# tripwire-alarm.net
KiCad netlist of a schematic drawn in EasyEDA
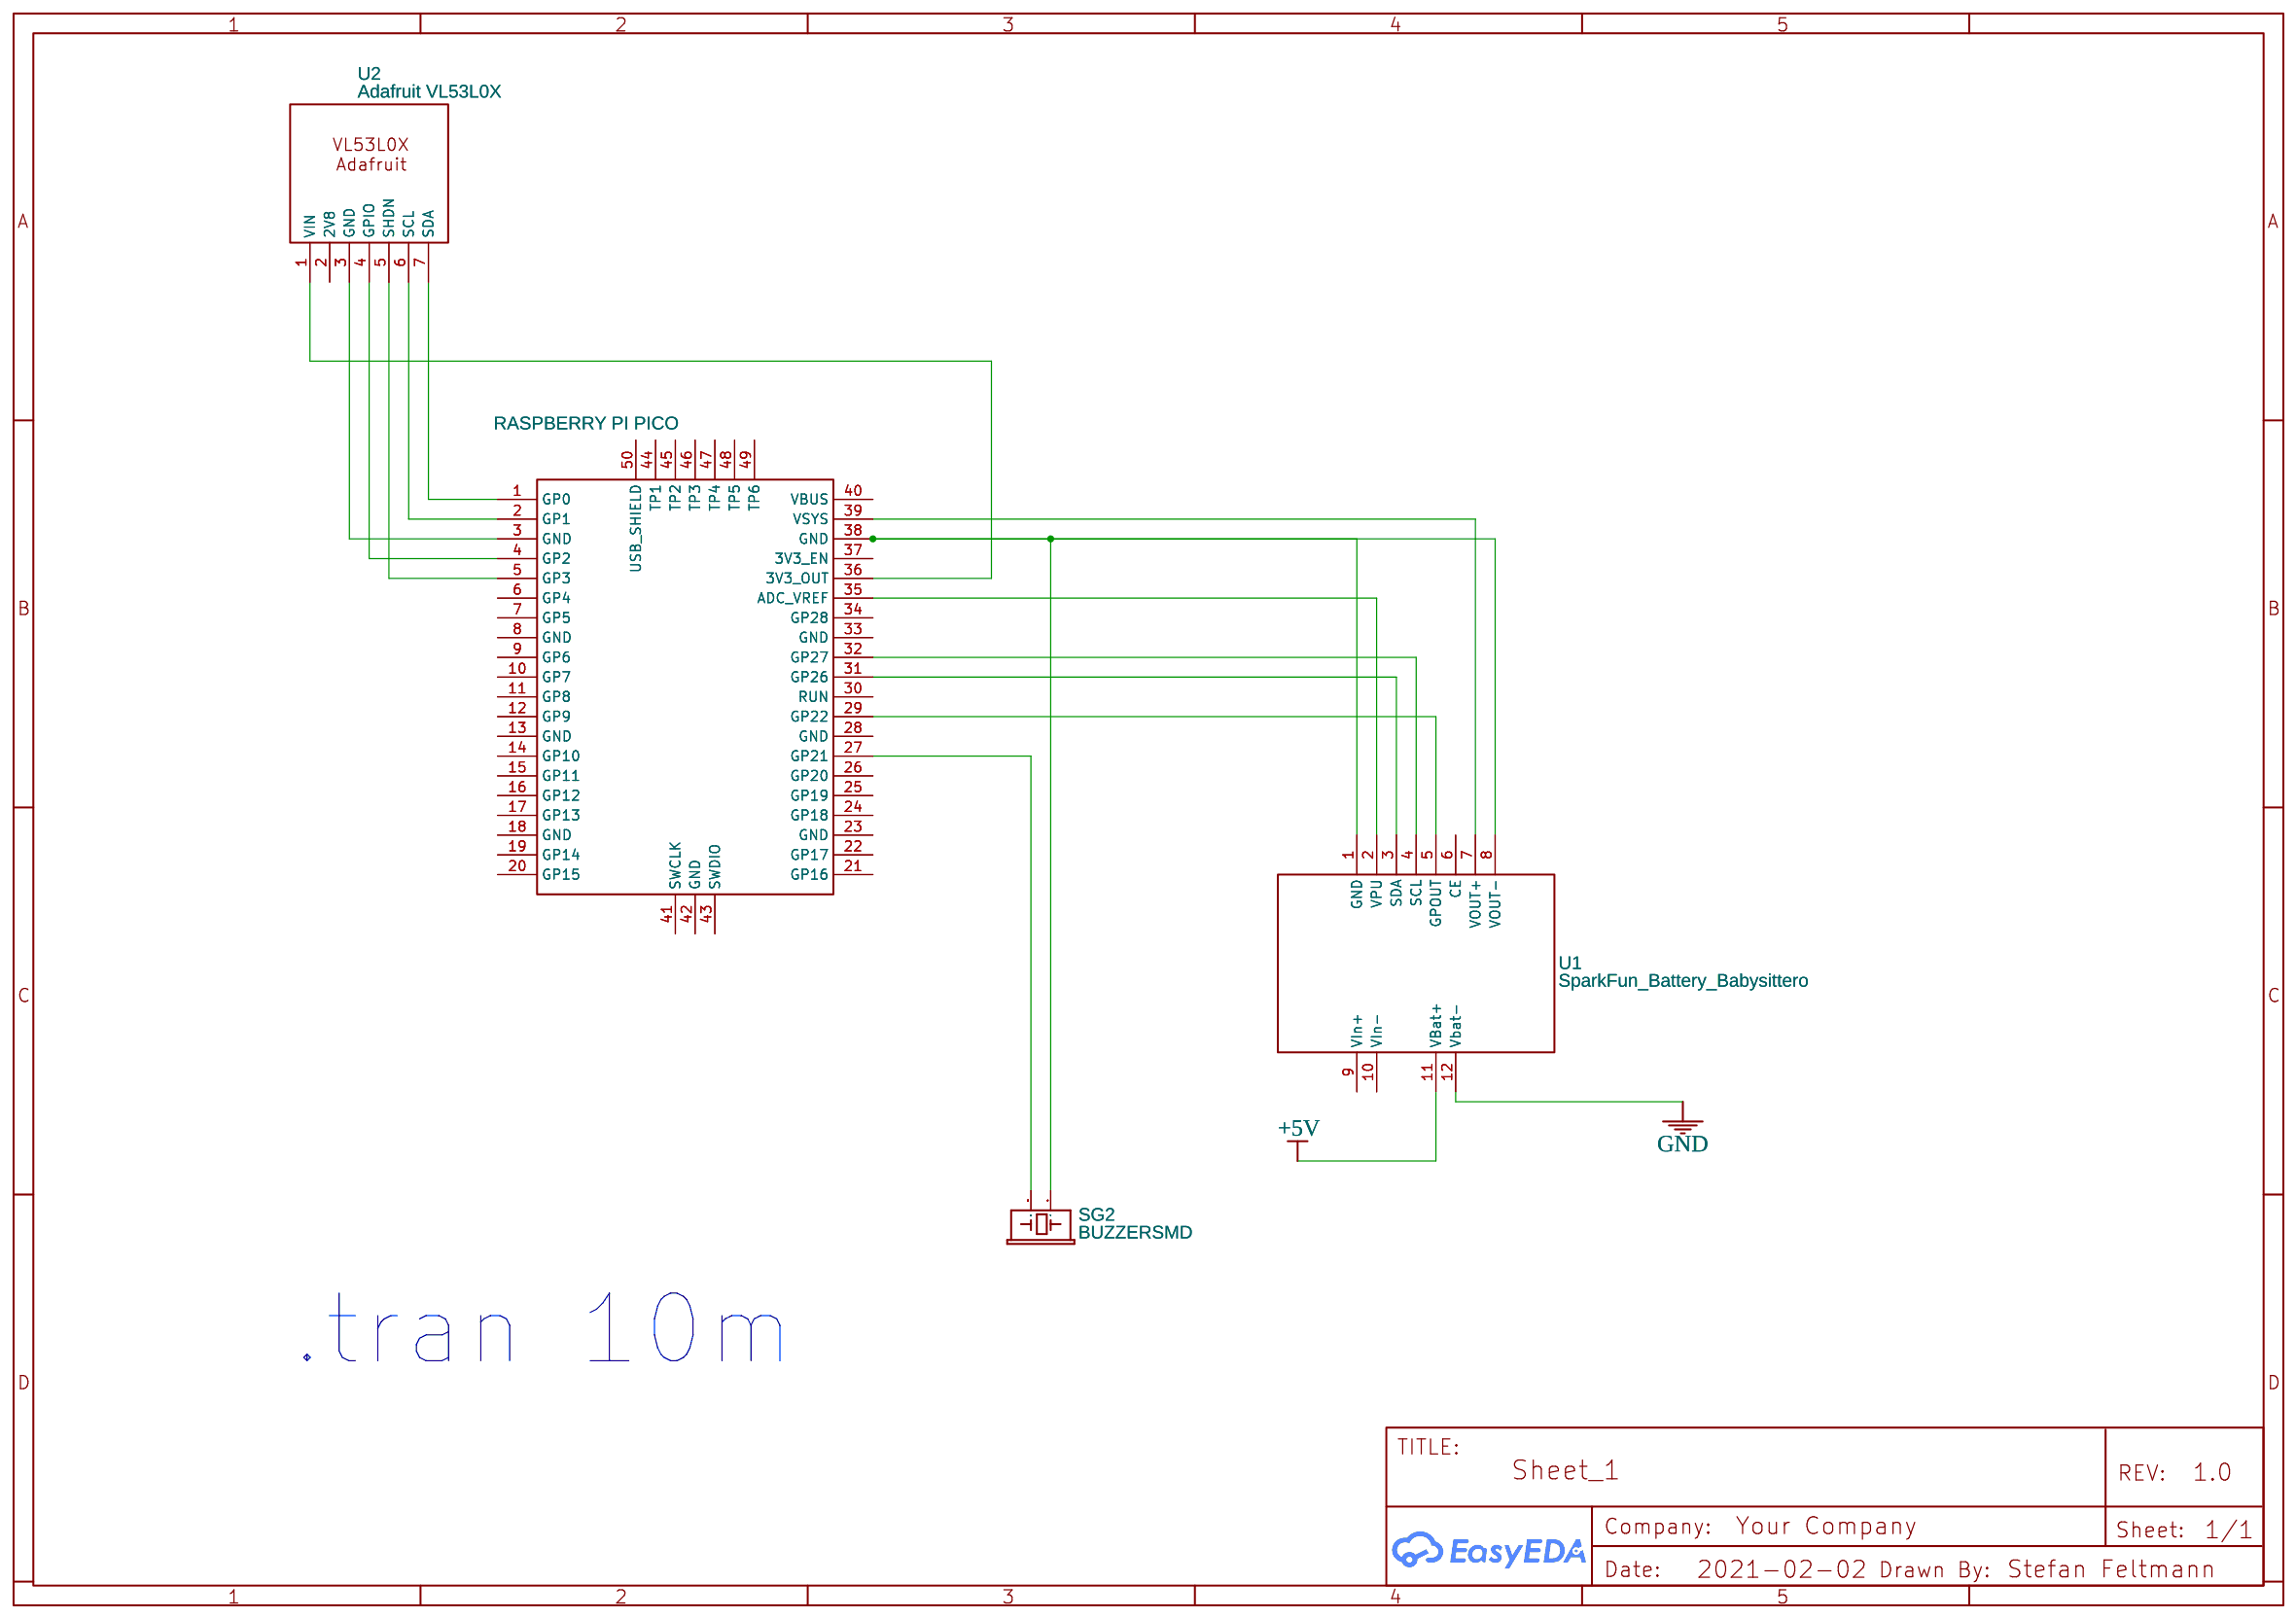
[diagram p0: schematic sheet]

(export (version "E")
  (design (tool "Eeschema 10.0.6"))
  (components
    (comp (ref "GP1")
      (value "RASPBERRY PI PICO")
      (fields (field (name "BOM_Manufacturer Part") "RPi Pico"))
      (libsource (lib "") (part "RASPBERRY PI PICO"))
    )
    (comp (ref "SG2") (value "BUZZERSMD") (libsource (lib "") (part "BUZZERSMD")))
    (comp (ref "U1")
      (value "SparkFun_Battery_Babysittero")
      (fields (field (name "BOM_Manufacturer Part") "SparkFun"))
      (libsource (lib "") (part "SparkFun_Battery_Babysittero"))
    )
    (comp (ref "U2")
      (value "Adafruit VL53L0X")
      (fields (field (name "BOM_Manufacturer Part") "3317"))
      (libsource (lib "") (part "Adafruit VL53L0X"))
    )
  )
  (nets
    (net (code "1") (name "+5V") (class "Default")
      (node (ref "U1") (pin "11") (pinfunction "VBat+_11") (pintype "unspecified"))
    )
    (net (code "2") (name "GND") (class "Default")
      (node (ref "U1") (pin "12") (pinfunction "Vbat-_12") (pintype "unspecified"))
    )
    (net (code "3") (name "Net-(GP1-3V3_OUT)") (class "Default")
      (node (ref "GP1") (pin "36") (pinfunction "3V3_OUT_36") (pintype "unspecified"))
      (node (ref "U2") (pin "1") (pinfunction "VIN_1") (pintype "unspecified"))
    )
    (net (code "4") (name "Net-(GP1-ADC_VREF)") (class "Default")
      (node (ref "GP1") (pin "35") (pinfunction "ADC_VREF_35") (pintype "unspecified"))
      (node (ref "U1") (pin "2") (pinfunction "VPU_2") (pintype "unspecified"))
    )
    (net (code "5") (name "Net-(GP1-GP0)") (class "Default")
      (node (ref "GP1") (pin "1") (pinfunction "GP0_1") (pintype "unspecified"))
      (node (ref "U2") (pin "7") (pinfunction "SDA_7") (pintype "unspecified"))
    )
    (net (code "6") (name "Net-(GP1-GP1)") (class "Default")
      (node (ref "GP1") (pin "2") (pinfunction "GP1_2") (pintype "unspecified"))
      (node (ref "U2") (pin "6") (pinfunction "SCL_6") (pintype "unspecified"))
    )
    (net (code "7") (name "Net-(GP1-GP2)") (class "Default")
      (node (ref "GP1") (pin "4") (pinfunction "GP2_4") (pintype "unspecified"))
      (node (ref "U2") (pin "4") (pinfunction "GPIO_4") (pintype "unspecified"))
    )
    (net (code "8") (name "Net-(GP1-GP3)") (class "Default")
      (node (ref "GP1") (pin "5") (pinfunction "GP3_5") (pintype "unspecified"))
      (node (ref "U2") (pin "5") (pinfunction "SHDN_5") (pintype "unspecified"))
    )
    (net (code "9") (name "Net-(GP1-GP21)") (class "Default")
      (node (ref "GP1") (pin "27") (pinfunction "GP21_27") (pintype "unspecified"))
      (node (ref "SG2") (pin "P$2") (pinfunction "2_P$2") (pintype "unspecified"))
    )
    (net (code "10") (name "Net-(GP1-GP22)") (class "Default")
      (node (ref "GP1") (pin "29") (pinfunction "GP22_29") (pintype "unspecified"))
      (node (ref "U1") (pin "5") (pinfunction "GPOUT_5") (pintype "unspecified"))
    )
    (net (code "11") (name "Net-(GP1-GP26)") (class "Default")
      (node (ref "GP1") (pin "31") (pinfunction "GP26_31") (pintype "unspecified"))
      (node (ref "U1") (pin "3") (pinfunction "SDA_3") (pintype "unspecified"))
    )
    (net (code "12") (name "Net-(GP1-GP27)") (class "Default")
      (node (ref "GP1") (pin "32") (pinfunction "GP27_32") (pintype "unspecified"))
      (node (ref "U1") (pin "4") (pinfunction "SCL_4") (pintype "unspecified"))
    )
    (net (code "13") (name "Net-(GP1-VSYS)") (class "Default")
      (node (ref "GP1") (pin "39") (pinfunction "VSYS_39") (pintype "unspecified"))
      (node (ref "U1") (pin "7") (pinfunction "VOUT+_7") (pintype "unspecified"))
    )
    (net (code "14") (name "Net-(SG2-1)") (class "Default")
      (node (ref "GP1") (pin "38") (pinfunction "GND_38") (pintype "unspecified"))
      (node (ref "SG2") (pin "P$1") (pinfunction "1_P$1") (pintype "unspecified"))
      (node (ref "U1") (pin "1") (pinfunction "GND_1") (pintype "unspecified"))
      (node (ref "U1") (pin "8") (pinfunction "VOUT-_8") (pintype "unspecified"))
    )
    (net (code "15") (name "Net-(U2-GND)") (class "Default")
      (node (ref "GP1") (pin "3") (pinfunction "GND_3") (pintype "unspecified"))
      (node (ref "U2") (pin "3") (pinfunction "GND_3") (pintype "unspecified"))
    )
    (net (code "16") (name "unconnected-(GP1-3V3_EN-Pad37)") (class "Default")
      (node (ref "GP1") (pin "37") (pinfunction "3V3_EN_37") (pintype "unspecified"))
    )
    (net (code "17") (name "unconnected-(GP1-GND-Pad8)") (class "Default")
      (node (ref "GP1") (pin "8") (pinfunction "GND_8") (pintype "unspecified"))
    )
    (net (code "18") (name "unconnected-(GP1-GND-Pad13)") (class "Default")
      (node (ref "GP1") (pin "13") (pinfunction "GND_13") (pintype "unspecified"))
    )
    (net (code "19") (name "unconnected-(GP1-GND-Pad18)") (class "Default")
      (node (ref "GP1") (pin "18") (pinfunction "GND_18") (pintype "unspecified"))
    )
    (net (code "20") (name "unconnected-(GP1-GND-Pad23)") (class "Default")
      (node (ref "GP1") (pin "23") (pinfunction "GND_23") (pintype "unspecified"))
    )
    (net (code "21") (name "unconnected-(GP1-GND-Pad28)") (class "Default")
      (node (ref "GP1") (pin "28") (pinfunction "GND_28") (pintype "unspecified"))
    )
    (net (code "22") (name "unconnected-(GP1-GND-Pad33)") (class "Default")
      (node (ref "GP1") (pin "33") (pinfunction "GND_33") (pintype "unspecified"))
    )
    (net (code "23") (name "unconnected-(GP1-GND-Pad42)") (class "Default")
      (node (ref "GP1") (pin "42") (pinfunction "GND_42") (pintype "unspecified"))
    )
    (net (code "24") (name "unconnected-(GP1-GP4-Pad6)") (class "Default")
      (node (ref "GP1") (pin "6") (pinfunction "GP4_6") (pintype "unspecified"))
    )
    (net (code "25") (name "unconnected-(GP1-GP5-Pad7)") (class "Default")
      (node (ref "GP1") (pin "7") (pinfunction "GP5_7") (pintype "unspecified"))
    )
    (net (code "26") (name "unconnected-(GP1-GP6-Pad9)") (class "Default")
      (node (ref "GP1") (pin "9") (pinfunction "GP6_9") (pintype "unspecified"))
    )
    (net (code "27") (name "unconnected-(GP1-GP7-Pad10)") (class "Default")
      (node (ref "GP1") (pin "10") (pinfunction "GP7_10") (pintype "unspecified"))
    )
    (net (code "28") (name "unconnected-(GP1-GP8-Pad11)") (class "Default")
      (node (ref "GP1") (pin "11") (pinfunction "GP8_11") (pintype "unspecified"))
    )
    (net (code "29") (name "unconnected-(GP1-GP9-Pad12)") (class "Default")
      (node (ref "GP1") (pin "12") (pinfunction "GP9_12") (pintype "unspecified"))
    )
    (net (code "30") (name "unconnected-(GP1-GP10-Pad14)") (class "Default")
      (node (ref "GP1") (pin "14") (pinfunction "GP10_14") (pintype "unspecified"))
    )
    (net (code "31") (name "unconnected-(GP1-GP11-Pad15)") (class "Default")
      (node (ref "GP1") (pin "15") (pinfunction "GP11_15") (pintype "unspecified"))
    )
    (net (code "32") (name "unconnected-(GP1-GP12-Pad16)") (class "Default")
      (node (ref "GP1") (pin "16") (pinfunction "GP12_16") (pintype "unspecified"))
    )
    (net (code "33") (name "unconnected-(GP1-GP13-Pad17)") (class "Default")
      (node (ref "GP1") (pin "17") (pinfunction "GP13_17") (pintype "unspecified"))
    )
    (net (code "34") (name "unconnected-(GP1-GP14-Pad19)") (class "Default")
      (node (ref "GP1") (pin "19") (pinfunction "GP14_19") (pintype "unspecified"))
    )
    (net (code "35") (name "unconnected-(GP1-GP15-Pad20)") (class "Default")
      (node (ref "GP1") (pin "20") (pinfunction "GP15_20") (pintype "unspecified"))
    )
    (net (code "36") (name "unconnected-(GP1-GP16-Pad21)") (class "Default")
      (node (ref "GP1") (pin "21") (pinfunction "GP16_21") (pintype "unspecified"))
    )
    (net (code "37") (name "unconnected-(GP1-GP17-Pad22)") (class "Default")
      (node (ref "GP1") (pin "22") (pinfunction "GP17_22") (pintype "unspecified"))
    )
    (net (code "38") (name "unconnected-(GP1-GP18-Pad24)") (class "Default")
      (node (ref "GP1") (pin "24") (pinfunction "GP18_24") (pintype "unspecified"))
    )
    (net (code "39") (name "unconnected-(GP1-GP19-Pad25)") (class "Default")
      (node (ref "GP1") (pin "25") (pinfunction "GP19_25") (pintype "unspecified"))
    )
    (net (code "40") (name "unconnected-(GP1-GP20-Pad26)") (class "Default")
      (node (ref "GP1") (pin "26") (pinfunction "GP20_26") (pintype "unspecified"))
    )
    (net (code "41") (name "unconnected-(GP1-GP28-Pad34)") (class "Default")
      (node (ref "GP1") (pin "34") (pinfunction "GP28_34") (pintype "unspecified"))
    )
    (net (code "42") (name "unconnected-(GP1-RUN-Pad30)") (class "Default")
      (node (ref "GP1") (pin "30") (pinfunction "RUN_30") (pintype "unspecified"))
    )
    (net (code "43") (name "unconnected-(GP1-SWCLK-Pad41)") (class "Default")
      (node (ref "GP1") (pin "41") (pinfunction "SWCLK_41") (pintype "unspecified"))
    )
    (net (code "44") (name "unconnected-(GP1-SWDIO-Pad43)") (class "Default")
      (node (ref "GP1") (pin "43") (pinfunction "SWDIO_43") (pintype "unspecified"))
    )
    (net (code "45") (name "unconnected-(GP1-TP1-Pad44)") (class "Default")
      (node (ref "GP1") (pin "44") (pinfunction "TP1_44") (pintype "unspecified"))
    )
    (net (code "46") (name "unconnected-(GP1-TP2-Pad45)") (class "Default")
      (node (ref "GP1") (pin "45") (pinfunction "TP2_45") (pintype "unspecified"))
    )
    (net (code "47") (name "unconnected-(GP1-TP3-Pad46)") (class "Default")
      (node (ref "GP1") (pin "46") (pinfunction "TP3_46") (pintype "unspecified"))
    )
    (net (code "48") (name "unconnected-(GP1-TP4-Pad47)") (class "Default")
      (node (ref "GP1") (pin "47") (pinfunction "TP4_47") (pintype "unspecified"))
    )
    (net (code "49") (name "unconnected-(GP1-TP5-Pad48)") (class "Default")
      (node (ref "GP1") (pin "48") (pinfunction "TP5_48") (pintype "unspecified"))
    )
    (net (code "50") (name "unconnected-(GP1-TP6-Pad49)") (class "Default")
      (node (ref "GP1") (pin "49") (pinfunction "TP6_49") (pintype "unspecified"))
    )
    (net (code "51") (name "unconnected-(GP1-USB_SHIELD-Pad50)") (class "Default")
      (node (ref "GP1") (pin "50") (pinfunction "USB_SHIELD_50") (pintype "unspecified"))
    )
    (net (code "52") (name "unconnected-(GP1-VBUS-Pad40)") (class "Default")
      (node (ref "GP1") (pin "40") (pinfunction "VBUS_40") (pintype "unspecified"))
    )
    (net (code "53") (name "unconnected-(U1-CE-Pad6)") (class "Default")
      (node (ref "U1") (pin "6") (pinfunction "CE_6") (pintype "unspecified"))
    )
    (net (code "54") (name "unconnected-(U1-VIn+-Pad9)") (class "Default")
      (node (ref "U1") (pin "9") (pinfunction "VIn+_9") (pintype "unspecified"))
    )
    (net (code "55") (name "unconnected-(U1-VIn--Pad10)") (class "Default")
      (node (ref "U1") (pin "10") (pinfunction "VIn-_10") (pintype "unspecified"))
    )
    (net (code "56") (name "unconnected-(U2-2V8-Pad2)") (class "Default")
      (node (ref "U2") (pin "2") (pinfunction "2V8_2") (pintype "unspecified"))
    )
  )
)
